# DebuggerKB.net
KiCad netlist of a schematic drawn in EAGLE
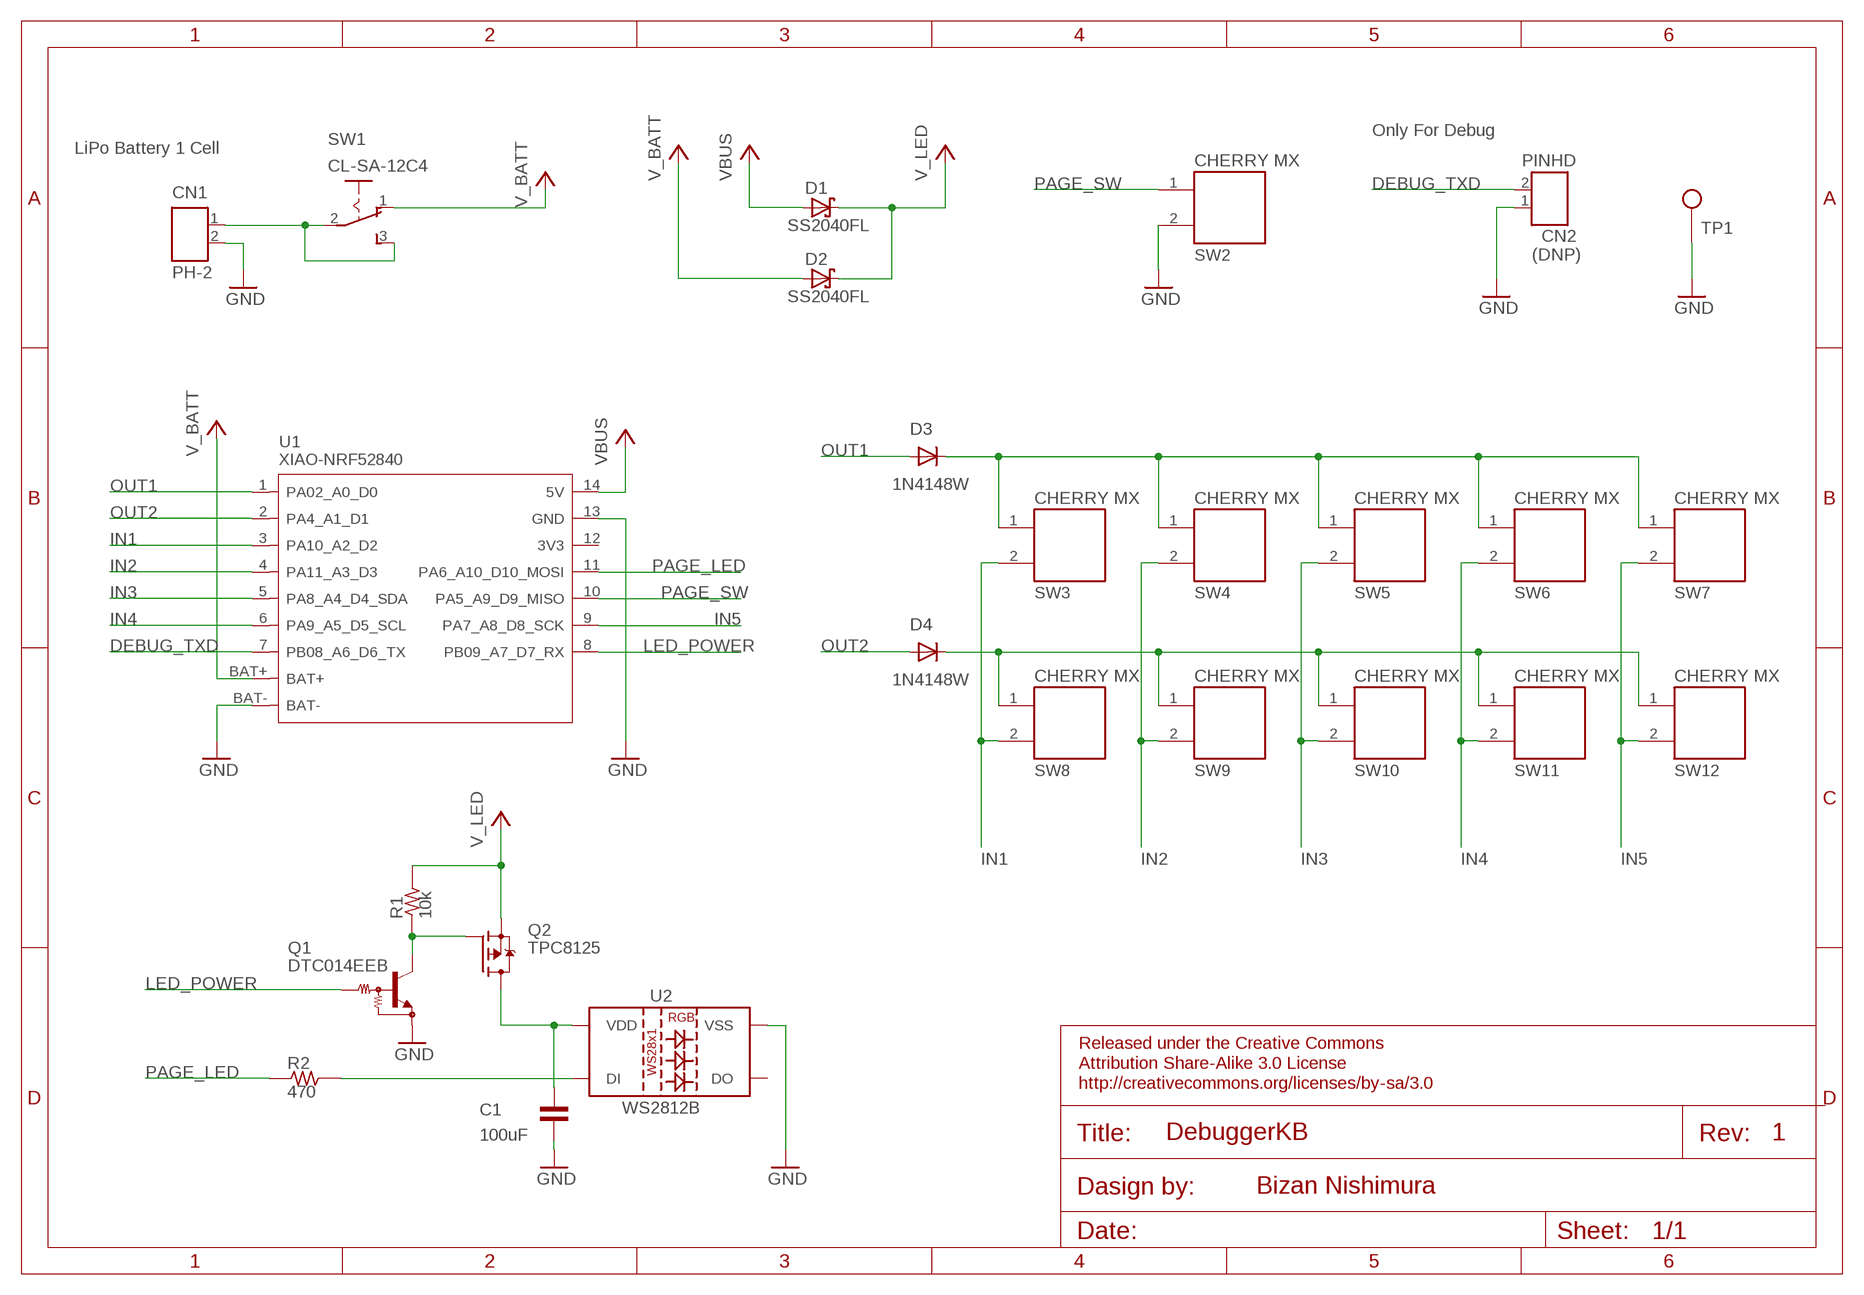
[diagram p0: schematic, sheet 1]

(export (version "E")
  (design (tool "Eeschema 10.0.6"))
  (components
    (comp (ref "C1")
      (value "100uF")
      (footprint "eagle-import:CP3216")
      (libsource (lib "eagle-import") (part "C-CP-3216"))
    )
    (comp (ref "CN1")
      (value "PH-2")
      (footprint "eagle-import:PH-2")
      (libsource (lib "eagle-import") (part "PH-2"))
    )
    (comp (ref "CN2")
      (value "PINHD")
      (footprint "eagle-import:1X02")
      (libsource (lib "eagle-import") (part "PINHD-1X2"))
    )
    (comp (ref "D1")
      (value "SS2040FL")
      (footprint "eagle-import:SOD123")
      (libsource (lib "eagle-import") (part "SCHOTTKY-DIODE-SOD123"))
    )
    (comp (ref "D2")
      (value "SS2040FL")
      (footprint "eagle-import:SOD123")
      (libsource (lib "eagle-import") (part "SCHOTTKY-DIODE-SOD123"))
    )
    (comp (ref "D3")
      (value "1N4148W")
      (footprint "eagle-import:SOD123")
      (libsource (lib "eagle-import") (part "DIODE-SOD123"))
    )
    (comp (ref "D4")
      (value "1N4148W")
      (footprint "eagle-import:SOD123")
      (libsource (lib "eagle-import") (part "DIODE-SOD123"))
    )
    (comp (ref "Q1")
      (value "DTC014EEB")
      (footprint "eagle-import:SOT490")
      (libsource (lib "eagle-import") (part "DIGITORASC89"))
    )
    (comp (ref "Q2")
      (value "TPC8125")
      (footprint "eagle-import:SO-8")
      (libsource (lib "eagle-import") (part "TPC8125"))
    )
    (comp (ref "R1")
      (value "10k")
      (footprint "eagle-import:CP1608")
      (libsource (lib "eagle-import") (part "R-CP-1608"))
    )
    (comp (ref "R2")
      (value "470")
      (footprint "eagle-import:CP1608")
      (libsource (lib "eagle-import") (part "R-CP-1608"))
    )
    (comp (ref "SW1")
      (value "CL-SA-12C4")
      (footprint "eagle-import:CL-SA-12C4")
      (libsource (lib "eagle-import") (part "CL-SA-12C4"))
    )
    (comp (ref "SW2")
      (value "KAILH_SWITCH_SOCKET")
      (footprint "eagle-import:SWITCH_SOCKET")
      (libsource (lib "eagle-import") (part "KAILH_SWITCH_SOCKET"))
    )
    (comp (ref "SW3")
      (value "KAILH_SWITCH_SOCKET")
      (footprint "eagle-import:SWITCH_SOCKET")
      (libsource (lib "eagle-import") (part "KAILH_SWITCH_SOCKET"))
    )
    (comp (ref "SW4")
      (value "KAILH_SWITCH_SOCKET")
      (footprint "eagle-import:SWITCH_SOCKET")
      (libsource (lib "eagle-import") (part "KAILH_SWITCH_SOCKET"))
    )
    (comp (ref "SW5")
      (value "KAILH_SWITCH_SOCKET")
      (footprint "eagle-import:SWITCH_SOCKET")
      (libsource (lib "eagle-import") (part "KAILH_SWITCH_SOCKET"))
    )
    (comp (ref "SW6")
      (value "KAILH_SWITCH_SOCKET")
      (footprint "eagle-import:SWITCH_SOCKET")
      (libsource (lib "eagle-import") (part "KAILH_SWITCH_SOCKET"))
    )
    (comp (ref "SW7")
      (value "KAILH_SWITCH_SOCKET")
      (footprint "eagle-import:SWITCH_SOCKET")
      (libsource (lib "eagle-import") (part "KAILH_SWITCH_SOCKET"))
    )
    (comp (ref "SW8")
      (value "KAILH_SWITCH_SOCKET")
      (footprint "eagle-import:SWITCH_SOCKET")
      (libsource (lib "eagle-import") (part "KAILH_SWITCH_SOCKET"))
    )
    (comp (ref "SW9")
      (value "KAILH_SWITCH_SOCKET")
      (footprint "eagle-import:SWITCH_SOCKET")
      (libsource (lib "eagle-import") (part "KAILH_SWITCH_SOCKET"))
    )
    (comp (ref "SW10")
      (value "KAILH_SWITCH_SOCKET")
      (footprint "eagle-import:SWITCH_SOCKET")
      (libsource (lib "eagle-import") (part "KAILH_SWITCH_SOCKET"))
    )
    (comp (ref "SW11")
      (value "KAILH_SWITCH_SOCKET")
      (footprint "eagle-import:SWITCH_SOCKET")
      (libsource (lib "eagle-import") (part "KAILH_SWITCH_SOCKET"))
    )
    (comp (ref "SW12")
      (value "KAILH_SWITCH_SOCKET")
      (footprint "eagle-import:SWITCH_SOCKET")
      (libsource (lib "eagle-import") (part "KAILH_SWITCH_SOCKET"))
    )
    (comp (ref "TP1")
      (value "TEST_PIN")
      (footprint "eagle-import:TEST_PIN")
      (libsource (lib "eagle-import") (part "TEST_PIN"))
    )
    (comp (ref "U1")
      (value "XIAO-NRF52840")
      (footprint "eagle-import:XIAO-NRF52840-BAT")
      (libsource (lib "eagle-import") (part "XIAO-NRF52840-BAT"))
    )
    (comp (ref "U2")
      (value "WS2812B")
      (footprint "eagle-import:WS2812B")
      (libsource (lib "eagle-import") (part "WS2812B"))
    )
  )
  (nets
    (net (code "1") (name "/DEBUG_TXD") (class "Default")
      (node (ref "CN2") (pin "2") (pinfunction "2_2") (pintype "bidirectional"))
      (node (ref "U1") (pin "7") (pinfunction "PB08_A6_D6_TX_7") (pintype "bidirectional"))
    )
    (net (code "2") (name "/IN1") (class "Default")
      (node (ref "SW3") (pin "2") (pinfunction "PIN-2_2") (pintype "bidirectional"))
      (node (ref "SW8") (pin "2") (pinfunction "PIN-2_2") (pintype "bidirectional"))
      (node (ref "U1") (pin "3") (pinfunction "PA10_A2_D2_3") (pintype "bidirectional"))
    )
    (net (code "3") (name "/IN2") (class "Default")
      (node (ref "SW4") (pin "2") (pinfunction "PIN-2_2") (pintype "bidirectional"))
      (node (ref "SW9") (pin "2") (pinfunction "PIN-2_2") (pintype "bidirectional"))
      (node (ref "U1") (pin "4") (pinfunction "PA11_A3_D3_4") (pintype "bidirectional"))
    )
    (net (code "4") (name "/IN3") (class "Default")
      (node (ref "SW10") (pin "2") (pinfunction "PIN-2_2") (pintype "bidirectional"))
      (node (ref "SW5") (pin "2") (pinfunction "PIN-2_2") (pintype "bidirectional"))
      (node (ref "U1") (pin "5") (pinfunction "PA8_A4_D4_SDA_5") (pintype "bidirectional"))
    )
    (net (code "5") (name "/IN4") (class "Default")
      (node (ref "SW11") (pin "2") (pinfunction "PIN-2_2") (pintype "bidirectional"))
      (node (ref "SW6") (pin "2") (pinfunction "PIN-2_2") (pintype "bidirectional"))
      (node (ref "U1") (pin "6") (pinfunction "PA9_A5_D5_SCL_6") (pintype "bidirectional"))
    )
    (net (code "6") (name "/IN5") (class "Default")
      (node (ref "SW12") (pin "2") (pinfunction "PIN-2_2") (pintype "bidirectional"))
      (node (ref "SW7") (pin "2") (pinfunction "PIN-2_2") (pintype "bidirectional"))
      (node (ref "U1") (pin "9") (pinfunction "PA7_A8_D8_SCK_9") (pintype "bidirectional"))
    )
    (net (code "7") (name "/LED_POWER") (class "Default")
      (node (ref "Q1") (pin "1") (pinfunction "B_1") (pintype "passive"))
      (node (ref "U1") (pin "8") (pinfunction "PB09_A7_D7_RX_8") (pintype "bidirectional"))
    )
    (net (code "8") (name "/OUT1") (class "Default")
      (node (ref "D3") (pin "A") (pinfunction "A_A") (pintype "passive"))
      (node (ref "U1") (pin "1") (pinfunction "PA02_A0_D0_1") (pintype "bidirectional"))
    )
    (net (code "9") (name "/OUT2") (class "Default")
      (node (ref "D4") (pin "A") (pinfunction "A_A") (pintype "passive"))
      (node (ref "U1") (pin "2") (pinfunction "PA4_A1_D1_2") (pintype "bidirectional"))
    )
    (net (code "10") (name "/PAGE_LED") (class "Default")
      (node (ref "R2") (pin "SMD1") (pinfunction "PIN1_SMD1") (pintype "passive"))
      (node (ref "U1") (pin "11") (pinfunction "PA6_A10_D10_MOSI_11") (pintype "bidirectional"))
    )
    (net (code "11") (name "/PAGE_SW") (class "Default")
      (node (ref "SW2") (pin "1") (pinfunction "PIN-1_1") (pintype "bidirectional"))
      (node (ref "U1") (pin "10") (pinfunction "PA5_A9_D9_MISO_10") (pintype "bidirectional"))
    )
    (net (code "12") (name "GND") (class "Default")
      (node (ref "C1") (pin "SMD2") (pinfunction "PIN2_SMD2") (pintype "passive"))
      (node (ref "CN1") (pin "2") (pinfunction "2_2") (pintype "bidirectional"))
      (node (ref "CN2") (pin "1") (pinfunction "1_1") (pintype "bidirectional"))
      (node (ref "Q1") (pin "2") (pinfunction "E_2") (pintype "passive"))
      (node (ref "SW2") (pin "2") (pinfunction "PIN-2_2") (pintype "bidirectional"))
      (node (ref "TP1") (pin "1") (pinfunction "P$1_1") (pintype "bidirectional"))
      (node (ref "U1") (pin "13") (pinfunction "GND_13") (pintype "bidirectional"))
      (node (ref "U1") (pin "BAT-") (pinfunction "BAT-_BAT-") (pintype "bidirectional"))
      (node (ref "U2") (pin "3") (pinfunction "VSS_3") (pintype "bidirectional"))
    )
    (net (code "13") (name "Net-(C1-PIN1)") (class "Default")
      (node (ref "C1") (pin "SMD1") (pinfunction "PIN1_SMD1") (pintype "passive"))
      (node (ref "Q2") (pin "5") (pinfunction "D_5") (pintype "passive"))
      (node (ref "Q2") (pin "6") (pinfunction "D_6") (pintype "passive"))
      (node (ref "Q2") (pin "7") (pinfunction "D_7") (pintype "passive"))
      (node (ref "Q2") (pin "8") (pinfunction "D_8") (pintype "passive"))
      (node (ref "U2") (pin "1") (pinfunction "VDD_1") (pintype "bidirectional"))
    )
    (net (code "14") (name "Net-(Q1-C)") (class "Default")
      (node (ref "Q1") (pin "3") (pinfunction "C_3") (pintype "passive"))
      (node (ref "Q2") (pin "4") (pinfunction "G_4") (pintype "passive"))
      (node (ref "R1") (pin "SMD1") (pinfunction "PIN1_SMD1") (pintype "passive"))
    )
    (net (code "15") (name "Net-(R2-PIN2)") (class "Default")
      (node (ref "R2") (pin "SMD2") (pinfunction "PIN2_SMD2") (pintype "passive"))
      (node (ref "U2") (pin "4") (pinfunction "DI_4") (pintype "bidirectional"))
    )
    (net (code "16") (name "Net-(SW1-P)") (class "Default")
      (node (ref "CN1") (pin "1") (pinfunction "1_1") (pintype "bidirectional"))
      (node (ref "SW1") (pin "2") (pinfunction "P_2") (pintype "passive"))
      (node (ref "SW1") (pin "3") (pinfunction "S_3") (pintype "passive"))
    )
    (net (code "17") (name "Net-(SW3-PIN-1)") (class "Default")
      (node (ref "D3") (pin "C") (pinfunction "C_C") (pintype "passive"))
      (node (ref "SW3") (pin "1") (pinfunction "PIN-1_1") (pintype "bidirectional"))
      (node (ref "SW4") (pin "1") (pinfunction "PIN-1_1") (pintype "bidirectional"))
      (node (ref "SW5") (pin "1") (pinfunction "PIN-1_1") (pintype "bidirectional"))
      (node (ref "SW6") (pin "1") (pinfunction "PIN-1_1") (pintype "bidirectional"))
      (node (ref "SW7") (pin "1") (pinfunction "PIN-1_1") (pintype "bidirectional"))
    )
    (net (code "18") (name "Net-(SW10-PIN-1)") (class "Default")
      (node (ref "D4") (pin "C") (pinfunction "C_C") (pintype "passive"))
      (node (ref "SW10") (pin "1") (pinfunction "PIN-1_1") (pintype "bidirectional"))
      (node (ref "SW11") (pin "1") (pinfunction "PIN-1_1") (pintype "bidirectional"))
      (node (ref "SW12") (pin "1") (pinfunction "PIN-1_1") (pintype "bidirectional"))
      (node (ref "SW8") (pin "1") (pinfunction "PIN-1_1") (pintype "bidirectional"))
      (node (ref "SW9") (pin "1") (pinfunction "PIN-1_1") (pintype "bidirectional"))
    )
    (net (code "19") (name "VBUS") (class "Default")
      (node (ref "D1") (pin "A") (pinfunction "A_A") (pintype "passive"))
      (node (ref "U1") (pin "14") (pinfunction "5V_14") (pintype "bidirectional"))
    )
    (net (code "20") (name "V_BATT") (class "Default")
      (node (ref "D2") (pin "A") (pinfunction "A_A") (pintype "passive"))
      (node (ref "SW1") (pin "1") (pinfunction "O_1") (pintype "passive"))
      (node (ref "U1") (pin "BAT+") (pinfunction "BAT+_BAT+") (pintype "bidirectional"))
    )
    (net (code "21") (name "V_LED") (class "Default")
      (node (ref "D1") (pin "C") (pinfunction "C_C") (pintype "passive"))
      (node (ref "D2") (pin "C") (pinfunction "C_C") (pintype "passive"))
      (node (ref "Q2") (pin "1") (pinfunction "S_1") (pintype "passive"))
      (node (ref "Q2") (pin "2") (pinfunction "S_2") (pintype "passive"))
      (node (ref "Q2") (pin "3") (pinfunction "S_3") (pintype "passive"))
      (node (ref "R1") (pin "SMD2") (pinfunction "PIN2_SMD2") (pintype "passive"))
    )
    (net (code "22") (name "unconnected-(U1-3V3-Pad12)") (class "Default")
      (node (ref "U1") (pin "12") (pinfunction "3V3_12") (pintype "bidirectional"))
    )
    (net (code "23") (name "unconnected-(U2-DO-Pad2)") (class "Default")
      (node (ref "U2") (pin "2") (pinfunction "DO_2") (pintype "bidirectional"))
    )
  )
)
